# Bpod_Serial_Shield_r4.net
KiCad netlist of a schematic drawn in EAGLE
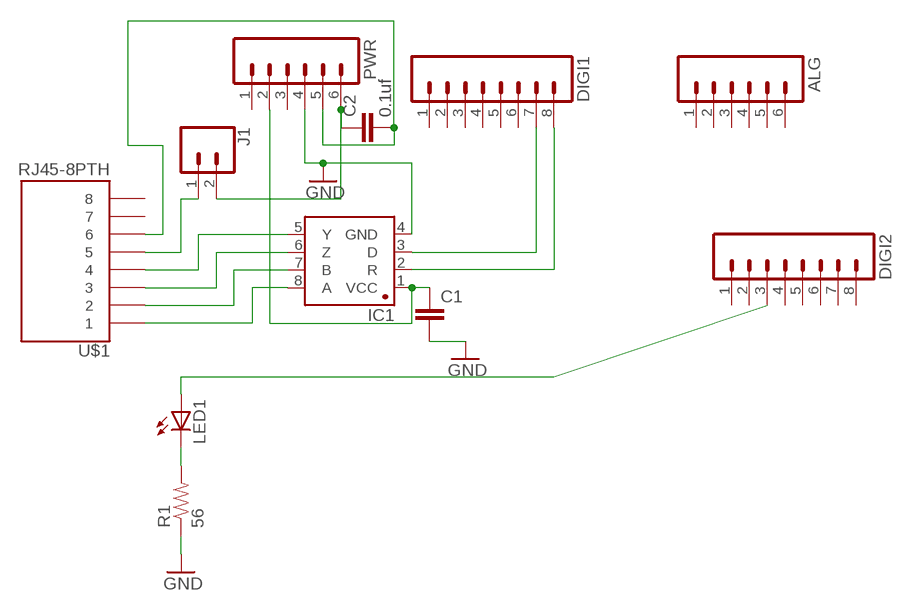
[diagram p0: schematic, sheet 1]

(export (version "E")
  (design (tool "Eeschema 10.0.6"))
  (components
    (comp (ref "ALG")
      (value "M06LONGPADS")
      (footprint "eagle-import:1X06_LONGPADS")
      (libsource (lib "eagle-import") (part "M06LONGPADS"))
    )
    (comp (ref "C1")
      (value "CAP1206")
      (footprint "eagle-import:1206")
      (libsource (lib "eagle-import") (part "CAP1206"))
    )
    (comp (ref "C2")
      (value "0.1uf")
      (footprint "eagle-import:1206")
      (libsource (lib "eagle-import") (part "CAP1206"))
    )
    (comp (ref "DIGI1")
      (value "M08LONGPADS")
      (footprint "eagle-import:1X08_LONGPADS")
      (libsource (lib "eagle-import") (part "M08LONGPADS"))
    )
    (comp (ref "DIGI2")
      (value "M08LONGPADS")
      (footprint "eagle-import:1X08_LONGPADS")
      (libsource (lib "eagle-import") (part "M08LONGPADS"))
    )
    (comp (ref "IC1")
      (value "SN65HVD31DR")
      (footprint "eagle-import:SO08")
      (libsource (lib "eagle-import") (part "SN65HVD31DR"))
    )
    (comp (ref "J1")
      (value "CONN_02")
      (footprint "eagle-import:1X02")
      (libsource (lib "eagle-import") (part "CONN_02"))
    )
    (comp (ref "LED1")
      (value "LEDCHIPLED_1206")
      (footprint "eagle-import:CHIPLED_1206")
      (libsource (lib "eagle-import") (part "LEDCHIPLED_1206"))
    )
    (comp (ref "PWR")
      (value "M06LONGPADS")
      (footprint "eagle-import:1X06_LONGPADS")
      (libsource (lib "eagle-import") (part "M06LONGPADS"))
    )
    (comp (ref "R1")
      (value "56")
      (footprint "eagle-import:1206")
      (libsource (lib "eagle-import") (part "RESISTOR1206"))
    )
    (comp (ref "U$1")
      (value "RJ45-8PTH")
      (footprint "eagle-import:RJ45-8")
      (libsource (lib "eagle-import") (part "RJ45-8PTH"))
    )
  )
  (nets
    (net (code "1") (name "GND") (class "Default")
      (node (ref "C1") (pin "2") (pinfunction "2_2") (pintype "passive"))
      (node (ref "IC1") (pin "4") (pinfunction "GND_4") (pintype "bidirectional"))
      (node (ref "PWR") (pin "4") (pinfunction "4_4") (pintype "passive"))
      (node (ref "R1") (pin "1") (pinfunction "1_1") (pintype "passive"))
    )
    (net (code "2") (name "Net-(C2-Pad1)") (class "Default")
      (node (ref "C2") (pin "1") (pinfunction "1_1") (pintype "passive"))
      (node (ref "J1") (pin "2") (pinfunction "2_2") (pintype "passive"))
      (node (ref "PWR") (pin "6") (pinfunction "6_6") (pintype "passive"))
    )
    (net (code "3") (name "Net-(C2-Pad2)") (class "Default")
      (node (ref "C2") (pin "2") (pinfunction "2_2") (pintype "passive"))
      (node (ref "PWR") (pin "5") (pinfunction "5_5") (pintype "passive"))
      (node (ref "U$1") (pin "6") (pinfunction "6_6") (pintype "bidirectional"))
    )
    (net (code "4") (name "Net-(DIGI2-Pad3)") (class "Default")
      (node (ref "DIGI2") (pin "3") (pinfunction "3_3") (pintype "passive"))
      (node (ref "LED1") (pin "A") (pinfunction "A_A") (pintype "passive"))
    )
    (net (code "5") (name "Net-(IC1-A)") (class "Default")
      (node (ref "IC1") (pin "8") (pinfunction "A_8") (pintype "bidirectional"))
      (node (ref "U$1") (pin "1") (pinfunction "1_1") (pintype "bidirectional"))
    )
    (net (code "6") (name "Net-(IC1-B)") (class "Default")
      (node (ref "IC1") (pin "7") (pinfunction "B_7") (pintype "bidirectional"))
      (node (ref "U$1") (pin "2") (pinfunction "2_2") (pintype "bidirectional"))
    )
    (net (code "7") (name "Net-(IC1-D)") (class "Default")
      (node (ref "DIGI1") (pin "7") (pinfunction "7_7") (pintype "passive"))
      (node (ref "IC1") (pin "3") (pinfunction "D_3") (pintype "bidirectional"))
    )
    (net (code "8") (name "Net-(IC1-R)") (class "Default")
      (node (ref "DIGI1") (pin "8") (pinfunction "8_8") (pintype "passive"))
      (node (ref "IC1") (pin "2") (pinfunction "R_2") (pintype "bidirectional"))
    )
    (net (code "9") (name "Net-(IC1-VCC)") (class "Default")
      (node (ref "C1") (pin "1") (pinfunction "1_1") (pintype "passive"))
      (node (ref "IC1") (pin "1") (pinfunction "VCC_1") (pintype "bidirectional"))
      (node (ref "PWR") (pin "2") (pinfunction "2_2") (pintype "passive"))
    )
    (net (code "10") (name "Net-(IC1-Y)") (class "Default")
      (node (ref "IC1") (pin "5") (pinfunction "Y_5") (pintype "bidirectional"))
      (node (ref "U$1") (pin "4") (pinfunction "4_4") (pintype "bidirectional"))
    )
    (net (code "11") (name "Net-(IC1-Z)") (class "Default")
      (node (ref "IC1") (pin "6") (pinfunction "Z_6") (pintype "bidirectional"))
      (node (ref "U$1") (pin "3") (pinfunction "3_3") (pintype "bidirectional"))
    )
    (net (code "12") (name "Net-(J1-Pad1)") (class "Default")
      (node (ref "J1") (pin "1") (pinfunction "1_1") (pintype "passive"))
      (node (ref "U$1") (pin "5") (pinfunction "5_5") (pintype "bidirectional"))
    )
    (net (code "13") (name "Net-(LED1-PadC)") (class "Default")
      (node (ref "LED1") (pin "C") (pinfunction "C_C") (pintype "passive"))
      (node (ref "R1") (pin "2") (pinfunction "2_2") (pintype "passive"))
    )
    (net (code "14") (name "unconnected-(ALG-Pad1)") (class "Default")
      (node (ref "ALG") (pin "1") (pinfunction "1_1") (pintype "passive"))
    )
    (net (code "15") (name "unconnected-(ALG-Pad2)") (class "Default")
      (node (ref "ALG") (pin "2") (pinfunction "2_2") (pintype "passive"))
    )
    (net (code "16") (name "unconnected-(ALG-Pad3)") (class "Default")
      (node (ref "ALG") (pin "3") (pinfunction "3_3") (pintype "passive"))
    )
    (net (code "17") (name "unconnected-(ALG-Pad4)") (class "Default")
      (node (ref "ALG") (pin "4") (pinfunction "4_4") (pintype "passive"))
    )
    (net (code "18") (name "unconnected-(ALG-Pad5)") (class "Default")
      (node (ref "ALG") (pin "5") (pinfunction "5_5") (pintype "passive"))
    )
    (net (code "19") (name "unconnected-(ALG-Pad6)") (class "Default")
      (node (ref "ALG") (pin "6") (pinfunction "6_6") (pintype "passive"))
    )
    (net (code "20") (name "unconnected-(DIGI1-Pad1)") (class "Default")
      (node (ref "DIGI1") (pin "1") (pinfunction "1_1") (pintype "passive"))
    )
    (net (code "21") (name "unconnected-(DIGI1-Pad2)") (class "Default")
      (node (ref "DIGI1") (pin "2") (pinfunction "2_2") (pintype "passive"))
    )
    (net (code "22") (name "unconnected-(DIGI1-Pad3)") (class "Default")
      (node (ref "DIGI1") (pin "3") (pinfunction "3_3") (pintype "passive"))
    )
    (net (code "23") (name "unconnected-(DIGI1-Pad4)") (class "Default")
      (node (ref "DIGI1") (pin "4") (pinfunction "4_4") (pintype "passive"))
    )
    (net (code "24") (name "unconnected-(DIGI1-Pad5)") (class "Default")
      (node (ref "DIGI1") (pin "5") (pinfunction "5_5") (pintype "passive"))
    )
    (net (code "25") (name "unconnected-(DIGI1-Pad6)") (class "Default")
      (node (ref "DIGI1") (pin "6") (pinfunction "6_6") (pintype "passive"))
    )
    (net (code "26") (name "unconnected-(DIGI2-Pad1)") (class "Default")
      (node (ref "DIGI2") (pin "1") (pinfunction "1_1") (pintype "passive"))
    )
    (net (code "27") (name "unconnected-(DIGI2-Pad2)") (class "Default")
      (node (ref "DIGI2") (pin "2") (pinfunction "2_2") (pintype "passive"))
    )
    (net (code "28") (name "unconnected-(DIGI2-Pad4)") (class "Default")
      (node (ref "DIGI2") (pin "4") (pinfunction "4_4") (pintype "passive"))
    )
    (net (code "29") (name "unconnected-(DIGI2-Pad5)") (class "Default")
      (node (ref "DIGI2") (pin "5") (pinfunction "5_5") (pintype "passive"))
    )
    (net (code "30") (name "unconnected-(DIGI2-Pad6)") (class "Default")
      (node (ref "DIGI2") (pin "6") (pinfunction "6_6") (pintype "passive"))
    )
    (net (code "31") (name "unconnected-(DIGI2-Pad7)") (class "Default")
      (node (ref "DIGI2") (pin "7") (pinfunction "7_7") (pintype "passive"))
    )
    (net (code "32") (name "unconnected-(DIGI2-Pad8)") (class "Default")
      (node (ref "DIGI2") (pin "8") (pinfunction "8_8") (pintype "passive"))
    )
    (net (code "33") (name "unconnected-(PWR-Pad1)") (class "Default")
      (node (ref "PWR") (pin "1") (pinfunction "1_1") (pintype "passive"))
    )
    (net (code "34") (name "unconnected-(PWR-Pad3)") (class "Default")
      (node (ref "PWR") (pin "3") (pinfunction "3_3") (pintype "passive"))
    )
    (net (code "35") (name "unconnected-(U$1-Pad7)") (class "Default")
      (node (ref "U$1") (pin "7") (pinfunction "7_7") (pintype "bidirectional"))
    )
    (net (code "36") (name "unconnected-(U$1-Pad8)") (class "Default")
      (node (ref "U$1") (pin "8") (pinfunction "8_8") (pintype "bidirectional"))
    )
  )
)
